# LM3404.net
KiCad netlist of a schematic drawn in EAGLE
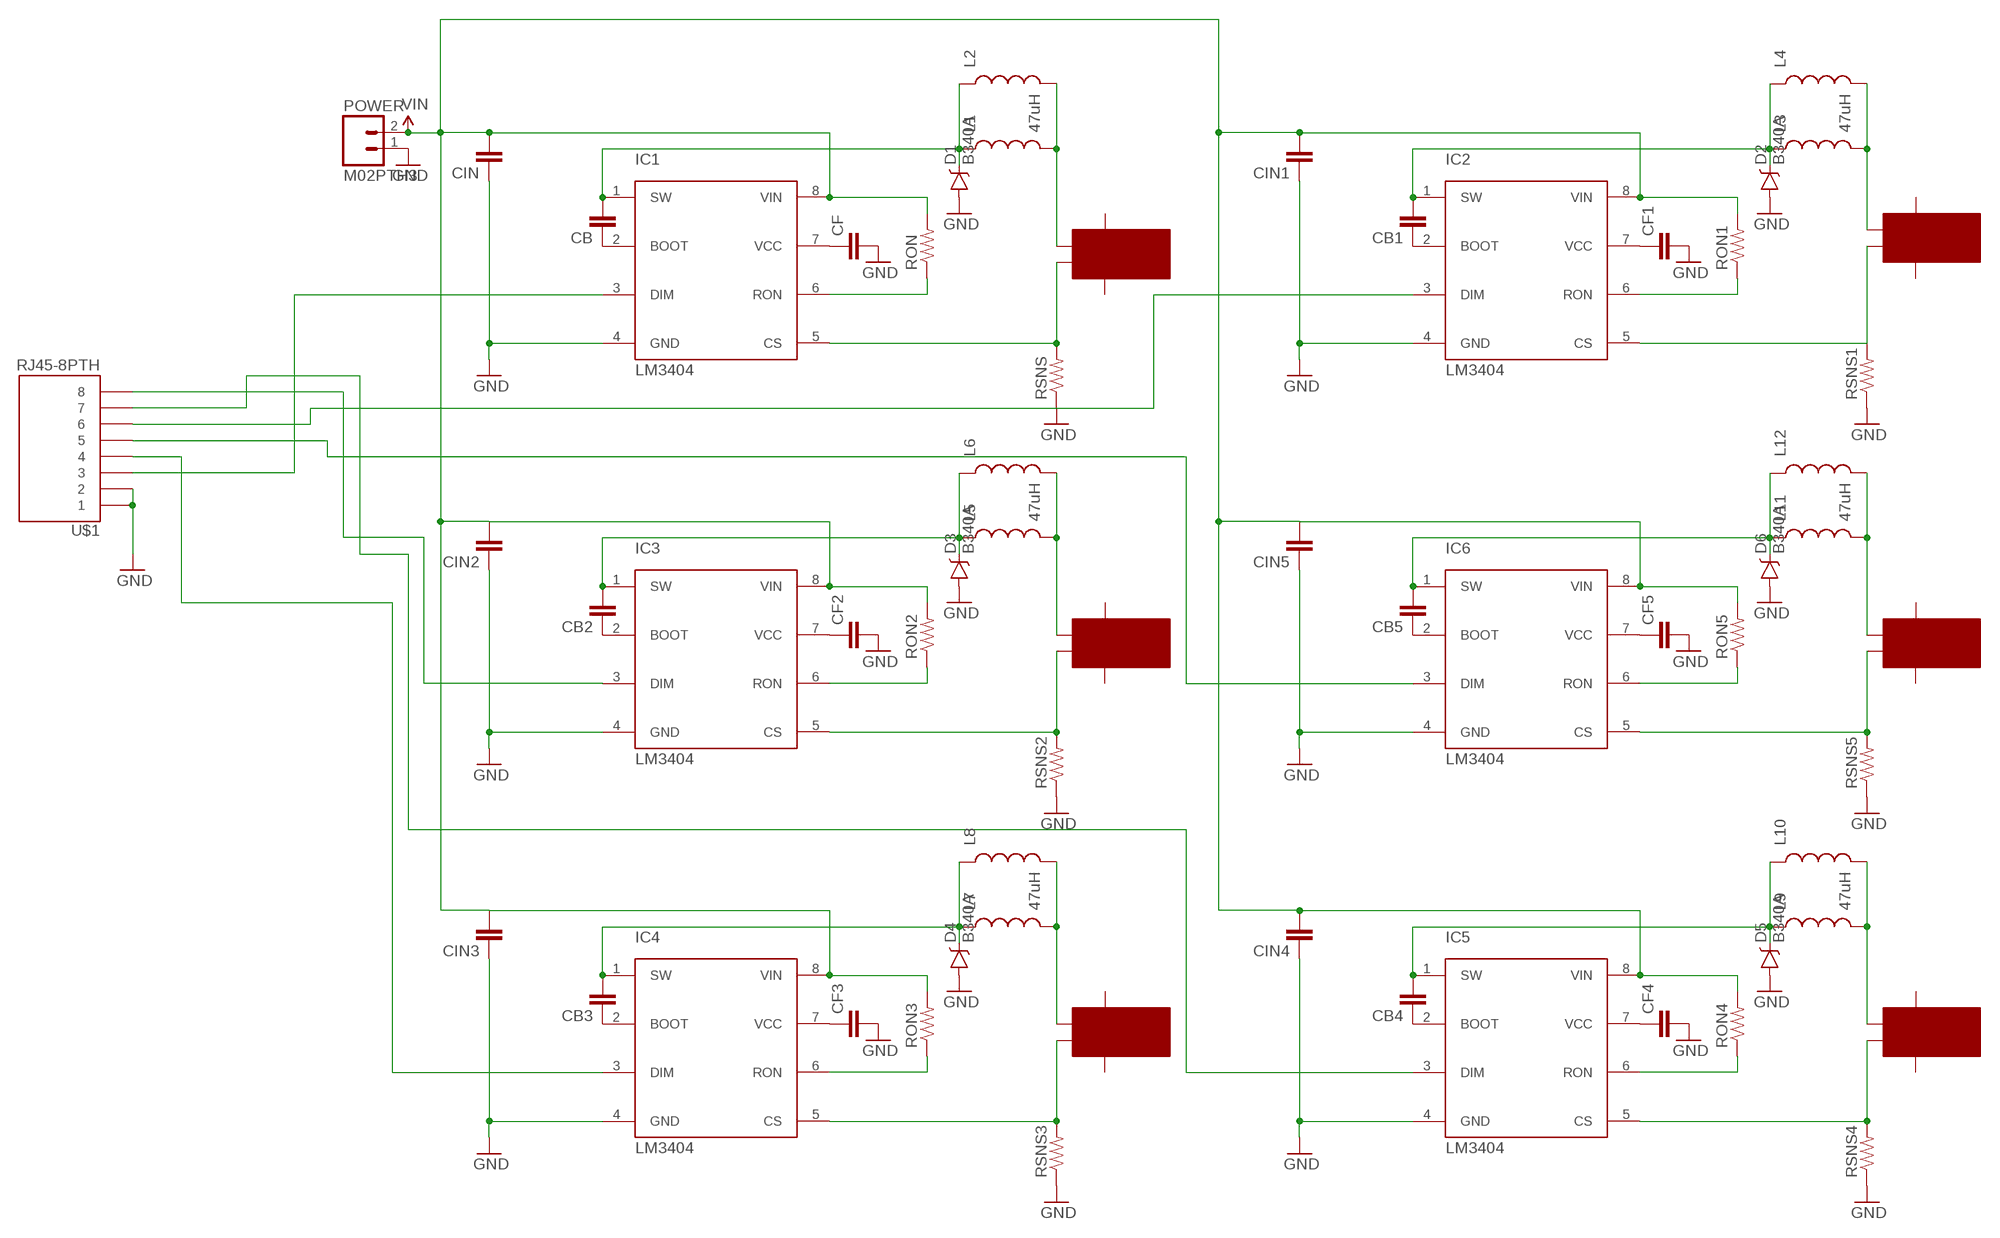
[diagram p0: schematic, sheet 1]

(export (version "E")
  (design (tool "Eeschema 10.0.6"))
  (components
    (comp (ref "CB")
      (value "CAP1206")
      (footprint "eagle-import:1206")
      (libsource (lib "eagle-import") (part "CAP1206"))
    )
    (comp (ref "CB1")
      (value "CAP1206")
      (footprint "eagle-import:1206")
      (libsource (lib "eagle-import") (part "CAP1206"))
    )
    (comp (ref "CB2")
      (value "CAP1206")
      (footprint "eagle-import:1206")
      (libsource (lib "eagle-import") (part "CAP1206"))
    )
    (comp (ref "CB3")
      (value "CAP1206")
      (footprint "eagle-import:1206")
      (libsource (lib "eagle-import") (part "CAP1206"))
    )
    (comp (ref "CB4")
      (value "CAP1206")
      (footprint "eagle-import:1206")
      (libsource (lib "eagle-import") (part "CAP1206"))
    )
    (comp (ref "CB5")
      (value "CAP1206")
      (footprint "eagle-import:1206")
      (libsource (lib "eagle-import") (part "CAP1206"))
    )
    (comp (ref "CF")
      (value "CAP1206")
      (footprint "eagle-import:1206")
      (libsource (lib "eagle-import") (part "CAP1206"))
    )
    (comp (ref "CF1")
      (value "CAP1206")
      (footprint "eagle-import:1206")
      (libsource (lib "eagle-import") (part "CAP1206"))
    )
    (comp (ref "CF2")
      (value "CAP1206")
      (footprint "eagle-import:1206")
      (libsource (lib "eagle-import") (part "CAP1206"))
    )
    (comp (ref "CF3")
      (value "CAP1206")
      (footprint "eagle-import:1206")
      (libsource (lib "eagle-import") (part "CAP1206"))
    )
    (comp (ref "CF4")
      (value "CAP1206")
      (footprint "eagle-import:1206")
      (libsource (lib "eagle-import") (part "CAP1206"))
    )
    (comp (ref "CF5")
      (value "CAP1206")
      (footprint "eagle-import:1206")
      (libsource (lib "eagle-import") (part "CAP1206"))
    )
    (comp (ref "CIN")
      (value "CAP1206")
      (footprint "eagle-import:1206")
      (libsource (lib "eagle-import") (part "CAP1206"))
    )
    (comp (ref "CIN1")
      (value "CAP1206")
      (footprint "eagle-import:1206")
      (libsource (lib "eagle-import") (part "CAP1206"))
    )
    (comp (ref "CIN2")
      (value "CAP1206")
      (footprint "eagle-import:1206")
      (libsource (lib "eagle-import") (part "CAP1206"))
    )
    (comp (ref "CIN3")
      (value "CAP1206")
      (footprint "eagle-import:1206")
      (libsource (lib "eagle-import") (part "CAP1206"))
    )
    (comp (ref "CIN4")
      (value "CAP1206")
      (footprint "eagle-import:1206")
      (libsource (lib "eagle-import") (part "CAP1206"))
    )
    (comp (ref "CIN5")
      (value "CAP1206")
      (footprint "eagle-import:1206")
      (libsource (lib "eagle-import") (part "CAP1206"))
    )
    (comp (ref "D1")
      (value "B340A")
      (footprint "eagle-import:SMA-DIODE")
      (libsource (lib "eagle-import") (part "DIODE-SCHOTTKY-B340A"))
    )
    (comp (ref "D2")
      (value "B340A")
      (footprint "eagle-import:SMA-DIODE")
      (libsource (lib "eagle-import") (part "DIODE-SCHOTTKY-B340A"))
    )
    (comp (ref "D3")
      (value "B340A")
      (footprint "eagle-import:SMA-DIODE")
      (libsource (lib "eagle-import") (part "DIODE-SCHOTTKY-B340A"))
    )
    (comp (ref "D4")
      (value "B340A")
      (footprint "eagle-import:SMA-DIODE")
      (libsource (lib "eagle-import") (part "DIODE-SCHOTTKY-B340A"))
    )
    (comp (ref "D5")
      (value "B340A")
      (footprint "eagle-import:SMA-DIODE")
      (libsource (lib "eagle-import") (part "DIODE-SCHOTTKY-B340A"))
    )
    (comp (ref "D6")
      (value "B340A")
      (footprint "eagle-import:SMA-DIODE")
      (libsource (lib "eagle-import") (part "DIODE-SCHOTTKY-B340A"))
    )
    (comp (ref "IC1")
      (value "LM3404")
      (footprint "eagle-import:SO8")
      (libsource (lib "eagle-import") (part "LM3404"))
    )
    (comp (ref "IC2")
      (value "LM3404")
      (footprint "eagle-import:SO8")
      (libsource (lib "eagle-import") (part "LM3404"))
    )
    (comp (ref "IC3")
      (value "LM3404")
      (footprint "eagle-import:SO8")
      (libsource (lib "eagle-import") (part "LM3404"))
    )
    (comp (ref "IC4")
      (value "LM3404")
      (footprint "eagle-import:SO8")
      (libsource (lib "eagle-import") (part "LM3404"))
    )
    (comp (ref "IC5")
      (value "LM3404")
      (footprint "eagle-import:SO8")
      (libsource (lib "eagle-import") (part "LM3404"))
    )
    (comp (ref "IC6")
      (value "LM3404")
      (footprint "eagle-import:SO8")
      (libsource (lib "eagle-import") (part "LM3404"))
    )
    (comp (ref "L1")
      (value "47uH")
      (footprint "eagle-import:CR75")
      (libsource (lib "eagle-import") (part "SparkFun-Passives_INDUCTOR68UH-1A"))
    )
    (comp (ref "L2")
      (value "INDUCTORSDR1105")
      (footprint "eagle-import:B82462G")
      (libsource (lib "eagle-import") (part "INDUCTORSDR1105"))
    )
    (comp (ref "L3")
      (value "47uH")
      (footprint "eagle-import:CR75")
      (libsource (lib "eagle-import") (part "SparkFun-Passives_INDUCTOR68UH-1A"))
    )
    (comp (ref "L4")
      (value "INDUCTORSDR1105")
      (footprint "eagle-import:B82462G")
      (libsource (lib "eagle-import") (part "INDUCTORSDR1105"))
    )
    (comp (ref "L5")
      (value "47uH")
      (footprint "eagle-import:CR75")
      (libsource (lib "eagle-import") (part "SparkFun-Passives_INDUCTOR68UH-1A"))
    )
    (comp (ref "L6")
      (value "INDUCTORSDR1105")
      (footprint "eagle-import:B82462G")
      (libsource (lib "eagle-import") (part "INDUCTORSDR1105"))
    )
    (comp (ref "L7")
      (value "47uH")
      (footprint "eagle-import:CR75")
      (libsource (lib "eagle-import") (part "SparkFun-Passives_INDUCTOR68UH-1A"))
    )
    (comp (ref "L8")
      (value "INDUCTORSDR1105")
      (footprint "eagle-import:B82462G")
      (libsource (lib "eagle-import") (part "INDUCTORSDR1105"))
    )
    (comp (ref "L9")
      (value "47uH")
      (footprint "eagle-import:CR75")
      (libsource (lib "eagle-import") (part "SparkFun-Passives_INDUCTOR68UH-1A"))
    )
    (comp (ref "L10")
      (value "INDUCTORSDR1105")
      (footprint "eagle-import:B82462G")
      (libsource (lib "eagle-import") (part "INDUCTORSDR1105"))
    )
    (comp (ref "L11")
      (value "47uH")
      (footprint "eagle-import:CR75")
      (libsource (lib "eagle-import") (part "SparkFun-Passives_INDUCTOR68UH-1A"))
    )
    (comp (ref "L12")
      (value "INDUCTORSDR1105")
      (footprint "eagle-import:B82462G")
      (libsource (lib "eagle-import") (part "INDUCTORSDR1105"))
    )
    (comp (ref "POWER")
      (value "M02PTH3")
      (footprint "eagle-import:1X02_LONGPADS")
      (libsource (lib "eagle-import") (part "M02PTH3"))
    )
    (comp (ref "RON")
      (value "RESISTOR1206")
      (footprint "eagle-import:1206")
      (libsource (lib "eagle-import") (part "RESISTOR1206"))
    )
    (comp (ref "RON1")
      (value "RESISTOR1206")
      (footprint "eagle-import:1206")
      (libsource (lib "eagle-import") (part "RESISTOR1206"))
    )
    (comp (ref "RON2")
      (value "RESISTOR1206")
      (footprint "eagle-import:1206")
      (libsource (lib "eagle-import") (part "RESISTOR1206"))
    )
    (comp (ref "RON3")
      (value "RESISTOR1206")
      (footprint "eagle-import:1206")
      (libsource (lib "eagle-import") (part "RESISTOR1206"))
    )
    (comp (ref "RON4")
      (value "RESISTOR1206")
      (footprint "eagle-import:1206")
      (libsource (lib "eagle-import") (part "RESISTOR1206"))
    )
    (comp (ref "RON5")
      (value "RESISTOR1206")
      (footprint "eagle-import:1206")
      (libsource (lib "eagle-import") (part "RESISTOR1206"))
    )
    (comp (ref "RSNS")
      (value "RESISTOR1206")
      (footprint "eagle-import:1206")
      (libsource (lib "eagle-import") (part "RESISTOR1206"))
    )
    (comp (ref "RSNS1")
      (value "RESISTOR1206")
      (footprint "eagle-import:1206")
      (libsource (lib "eagle-import") (part "RESISTOR1206"))
    )
    (comp (ref "RSNS2")
      (value "RESISTOR1206")
      (footprint "eagle-import:1206")
      (libsource (lib "eagle-import") (part "RESISTOR1206"))
    )
    (comp (ref "RSNS3")
      (value "RESISTOR1206")
      (footprint "eagle-import:1206")
      (libsource (lib "eagle-import") (part "RESISTOR1206"))
    )
    (comp (ref "RSNS4")
      (value "RESISTOR1206")
      (footprint "eagle-import:1206")
      (libsource (lib "eagle-import") (part "RESISTOR1206"))
    )
    (comp (ref "RSNS5")
      (value "RESISTOR1206")
      (footprint "eagle-import:1206")
      (libsource (lib "eagle-import") (part "RESISTOR1206"))
    )
    (comp (ref "U$1")
      (value "RJ45-8PTH")
      (footprint "eagle-import:RJ45-8")
      (libsource (lib "eagle-import") (part "RJ45-8PTH"))
    )
    (comp (ref "U$2")
      (value "RCA_JACK")
      (footprint "eagle-import:RCA_JACK")
      (libsource (lib "eagle-import") (part "RCA_JACK"))
    )
    (comp (ref "U$3")
      (value "RCA_JACK")
      (footprint "eagle-import:RCA_JACK")
      (libsource (lib "eagle-import") (part "RCA_JACK"))
    )
    (comp (ref "U$4")
      (value "RCA_JACK")
      (footprint "eagle-import:RCA_JACK")
      (libsource (lib "eagle-import") (part "RCA_JACK"))
    )
    (comp (ref "U$5")
      (value "RCA_JACK")
      (footprint "eagle-import:RCA_JACK")
      (libsource (lib "eagle-import") (part "RCA_JACK"))
    )
    (comp (ref "U$6")
      (value "RCA_JACK")
      (footprint "eagle-import:RCA_JACK")
      (libsource (lib "eagle-import") (part "RCA_JACK"))
    )
    (comp (ref "U$7")
      (value "RCA_JACK")
      (footprint "eagle-import:RCA_JACK")
      (libsource (lib "eagle-import") (part "RCA_JACK"))
    )
  )
  (nets
    (net (code "1") (name "GND") (class "Default")
      (node (ref "CF") (pin "2") (pinfunction "2_2") (pintype "passive"))
      (node (ref "CF1") (pin "2") (pinfunction "2_2") (pintype "passive"))
      (node (ref "CF2") (pin "2") (pinfunction "2_2") (pintype "passive"))
      (node (ref "CF3") (pin "2") (pinfunction "2_2") (pintype "passive"))
      (node (ref "CF4") (pin "2") (pinfunction "2_2") (pintype "passive"))
      (node (ref "CF5") (pin "2") (pinfunction "2_2") (pintype "passive"))
      (node (ref "CIN") (pin "1") (pinfunction "1_1") (pintype "passive"))
      (node (ref "CIN1") (pin "1") (pinfunction "1_1") (pintype "passive"))
      (node (ref "CIN2") (pin "1") (pinfunction "1_1") (pintype "passive"))
      (node (ref "CIN3") (pin "1") (pinfunction "1_1") (pintype "passive"))
      (node (ref "CIN4") (pin "1") (pinfunction "1_1") (pintype "passive"))
      (node (ref "CIN5") (pin "1") (pinfunction "1_1") (pintype "passive"))
      (node (ref "D1") (pin "A") (pinfunction "A_A") (pintype "passive"))
      (node (ref "D2") (pin "A") (pinfunction "A_A") (pintype "passive"))
      (node (ref "D3") (pin "A") (pinfunction "A_A") (pintype "passive"))
      (node (ref "D4") (pin "A") (pinfunction "A_A") (pintype "passive"))
      (node (ref "D5") (pin "A") (pinfunction "A_A") (pintype "passive"))
      (node (ref "D6") (pin "A") (pinfunction "A_A") (pintype "passive"))
      (node (ref "IC1") (pin "4") (pinfunction "GND_4") (pintype "bidirectional"))
      (node (ref "IC2") (pin "4") (pinfunction "GND_4") (pintype "bidirectional"))
      (node (ref "IC3") (pin "4") (pinfunction "GND_4") (pintype "bidirectional"))
      (node (ref "IC4") (pin "4") (pinfunction "GND_4") (pintype "bidirectional"))
      (node (ref "IC5") (pin "4") (pinfunction "GND_4") (pintype "bidirectional"))
      (node (ref "IC6") (pin "4") (pinfunction "GND_4") (pintype "bidirectional"))
      (node (ref "POWER") (pin "1") (pinfunction "1_1") (pintype "passive"))
      (node (ref "RSNS") (pin "1") (pinfunction "1_1") (pintype "passive"))
      (node (ref "RSNS1") (pin "1") (pinfunction "1_1") (pintype "passive"))
      (node (ref "RSNS2") (pin "1") (pinfunction "1_1") (pintype "passive"))
      (node (ref "RSNS3") (pin "1") (pinfunction "1_1") (pintype "passive"))
      (node (ref "RSNS4") (pin "1") (pinfunction "1_1") (pintype "passive"))
      (node (ref "RSNS5") (pin "1") (pinfunction "1_1") (pintype "passive"))
      (node (ref "U$1") (pin "1") (pinfunction "1_1") (pintype "bidirectional"))
      (node (ref "U$1") (pin "2") (pinfunction "2_2") (pintype "bidirectional"))
    )
    (net (code "2") (name "Net-(IC1-BOOT)") (class "Default")
      (node (ref "CB") (pin "1") (pinfunction "1_1") (pintype "passive"))
      (node (ref "IC1") (pin "2") (pinfunction "BOOT_2") (pintype "bidirectional"))
    )
    (net (code "3") (name "Net-(IC1-CS)") (class "Default")
      (node (ref "IC1") (pin "5") (pinfunction "CS_5") (pintype "bidirectional"))
      (node (ref "RSNS") (pin "2") (pinfunction "2_2") (pintype "passive"))
      (node (ref "U$7") (pin "INNER") (pinfunction "INNER_INNER") (pintype "bidirectional"))
    )
    (net (code "4") (name "Net-(IC1-DIM)") (class "Default")
      (node (ref "IC1") (pin "3") (pinfunction "DIM_3") (pintype "bidirectional"))
      (node (ref "U$1") (pin "3") (pinfunction "3_3") (pintype "bidirectional"))
    )
    (net (code "5") (name "Net-(IC1-RON)") (class "Default")
      (node (ref "IC1") (pin "6") (pinfunction "RON_6") (pintype "bidirectional"))
      (node (ref "RON") (pin "1") (pinfunction "1_1") (pintype "passive"))
    )
    (net (code "6") (name "Net-(IC1-SW)") (class "Default")
      (node (ref "CB") (pin "2") (pinfunction "2_2") (pintype "passive"))
      (node (ref "D1") (pin "C") (pinfunction "C_C") (pintype "passive"))
      (node (ref "IC1") (pin "1") (pinfunction "SW_1") (pintype "bidirectional"))
      (node (ref "L1") (pin "P$1") (pinfunction "1_P$1") (pintype "passive"))
      (node (ref "L2") (pin "P$1") (pinfunction "1_P$1") (pintype "passive"))
    )
    (net (code "7") (name "Net-(IC1-VCC)") (class "Default")
      (node (ref "CF") (pin "1") (pinfunction "1_1") (pintype "passive"))
      (node (ref "IC1") (pin "7") (pinfunction "VCC_7") (pintype "bidirectional"))
    )
    (net (code "8") (name "Net-(IC2-BOOT)") (class "Default")
      (node (ref "CB1") (pin "1") (pinfunction "1_1") (pintype "passive"))
      (node (ref "IC2") (pin "2") (pinfunction "BOOT_2") (pintype "bidirectional"))
    )
    (net (code "9") (name "Net-(IC2-CS)") (class "Default")
      (node (ref "IC2") (pin "5") (pinfunction "CS_5") (pintype "bidirectional"))
      (node (ref "RSNS1") (pin "2") (pinfunction "2_2") (pintype "passive"))
      (node (ref "U$2") (pin "INNER") (pinfunction "INNER_INNER") (pintype "bidirectional"))
    )
    (net (code "10") (name "Net-(IC2-DIM)") (class "Default")
      (node (ref "IC2") (pin "3") (pinfunction "DIM_3") (pintype "bidirectional"))
      (node (ref "U$1") (pin "6") (pinfunction "6_6") (pintype "bidirectional"))
    )
    (net (code "11") (name "Net-(IC2-RON)") (class "Default")
      (node (ref "IC2") (pin "6") (pinfunction "RON_6") (pintype "bidirectional"))
      (node (ref "RON1") (pin "1") (pinfunction "1_1") (pintype "passive"))
    )
    (net (code "12") (name "Net-(IC2-SW)") (class "Default")
      (node (ref "CB1") (pin "2") (pinfunction "2_2") (pintype "passive"))
      (node (ref "D2") (pin "C") (pinfunction "C_C") (pintype "passive"))
      (node (ref "IC2") (pin "1") (pinfunction "SW_1") (pintype "bidirectional"))
      (node (ref "L3") (pin "P$1") (pinfunction "1_P$1") (pintype "passive"))
      (node (ref "L4") (pin "P$1") (pinfunction "1_P$1") (pintype "passive"))
    )
    (net (code "13") (name "Net-(IC2-VCC)") (class "Default")
      (node (ref "CF1") (pin "1") (pinfunction "1_1") (pintype "passive"))
      (node (ref "IC2") (pin "7") (pinfunction "VCC_7") (pintype "bidirectional"))
    )
    (net (code "14") (name "Net-(IC3-BOOT)") (class "Default")
      (node (ref "CB2") (pin "1") (pinfunction "1_1") (pintype "passive"))
      (node (ref "IC3") (pin "2") (pinfunction "BOOT_2") (pintype "bidirectional"))
    )
    (net (code "15") (name "Net-(IC3-CS)") (class "Default")
      (node (ref "IC3") (pin "5") (pinfunction "CS_5") (pintype "bidirectional"))
      (node (ref "RSNS2") (pin "2") (pinfunction "2_2") (pintype "passive"))
      (node (ref "U$6") (pin "INNER") (pinfunction "INNER_INNER") (pintype "bidirectional"))
    )
    (net (code "16") (name "Net-(IC3-DIM)") (class "Default")
      (node (ref "IC3") (pin "3") (pinfunction "DIM_3") (pintype "bidirectional"))
      (node (ref "U$1") (pin "8") (pinfunction "8_8") (pintype "bidirectional"))
    )
    (net (code "17") (name "Net-(IC3-RON)") (class "Default")
      (node (ref "IC3") (pin "6") (pinfunction "RON_6") (pintype "bidirectional"))
      (node (ref "RON2") (pin "1") (pinfunction "1_1") (pintype "passive"))
    )
    (net (code "18") (name "Net-(IC3-SW)") (class "Default")
      (node (ref "CB2") (pin "2") (pinfunction "2_2") (pintype "passive"))
      (node (ref "D3") (pin "C") (pinfunction "C_C") (pintype "passive"))
      (node (ref "IC3") (pin "1") (pinfunction "SW_1") (pintype "bidirectional"))
      (node (ref "L5") (pin "P$1") (pinfunction "1_P$1") (pintype "passive"))
      (node (ref "L6") (pin "P$1") (pinfunction "1_P$1") (pintype "passive"))
    )
    (net (code "19") (name "Net-(IC3-VCC)") (class "Default")
      (node (ref "CF2") (pin "1") (pinfunction "1_1") (pintype "passive"))
      (node (ref "IC3") (pin "7") (pinfunction "VCC_7") (pintype "bidirectional"))
    )
    (net (code "20") (name "Net-(IC4-BOOT)") (class "Default")
      (node (ref "CB3") (pin "1") (pinfunction "1_1") (pintype "passive"))
      (node (ref "IC4") (pin "2") (pinfunction "BOOT_2") (pintype "bidirectional"))
    )
    (net (code "21") (name "Net-(IC4-CS)") (class "Default")
      (node (ref "IC4") (pin "5") (pinfunction "CS_5") (pintype "bidirectional"))
      (node (ref "RSNS3") (pin "2") (pinfunction "2_2") (pintype "passive"))
      (node (ref "U$5") (pin "INNER") (pinfunction "INNER_INNER") (pintype "bidirectional"))
    )
    (net (code "22") (name "Net-(IC4-DIM)") (class "Default")
      (node (ref "IC4") (pin "3") (pinfunction "DIM_3") (pintype "bidirectional"))
      (node (ref "U$1") (pin "4") (pinfunction "4_4") (pintype "bidirectional"))
    )
    (net (code "23") (name "Net-(IC4-RON)") (class "Default")
      (node (ref "IC4") (pin "6") (pinfunction "RON_6") (pintype "bidirectional"))
      (node (ref "RON3") (pin "1") (pinfunction "1_1") (pintype "passive"))
    )
    (net (code "24") (name "Net-(IC4-SW)") (class "Default")
      (node (ref "CB3") (pin "2") (pinfunction "2_2") (pintype "passive"))
      (node (ref "D4") (pin "C") (pinfunction "C_C") (pintype "passive"))
      (node (ref "IC4") (pin "1") (pinfunction "SW_1") (pintype "bidirectional"))
      (node (ref "L7") (pin "P$1") (pinfunction "1_P$1") (pintype "passive"))
      (node (ref "L8") (pin "P$1") (pinfunction "1_P$1") (pintype "passive"))
    )
    (net (code "25") (name "Net-(IC4-VCC)") (class "Default")
      (node (ref "CF3") (pin "1") (pinfunction "1_1") (pintype "passive"))
      (node (ref "IC4") (pin "7") (pinfunction "VCC_7") (pintype "bidirectional"))
    )
    (net (code "26") (name "Net-(IC5-BOOT)") (class "Default")
      (node (ref "CB4") (pin "1") (pinfunction "1_1") (pintype "passive"))
      (node (ref "IC5") (pin "2") (pinfunction "BOOT_2") (pintype "bidirectional"))
    )
    (net (code "27") (name "Net-(IC5-CS)") (class "Default")
      (node (ref "IC5") (pin "5") (pinfunction "CS_5") (pintype "bidirectional"))
      (node (ref "RSNS4") (pin "2") (pinfunction "2_2") (pintype "passive"))
      (node (ref "U$4") (pin "INNER") (pinfunction "INNER_INNER") (pintype "bidirectional"))
    )
    (net (code "28") (name "Net-(IC5-DIM)") (class "Default")
      (node (ref "IC5") (pin "3") (pinfunction "DIM_3") (pintype "bidirectional"))
      (node (ref "U$1") (pin "7") (pinfunction "7_7") (pintype "bidirectional"))
    )
    (net (code "29") (name "Net-(IC5-RON)") (class "Default")
      (node (ref "IC5") (pin "6") (pinfunction "RON_6") (pintype "bidirectional"))
      (node (ref "RON4") (pin "1") (pinfunction "1_1") (pintype "passive"))
    )
    (net (code "30") (name "Net-(IC5-SW)") (class "Default")
      (node (ref "CB4") (pin "2") (pinfunction "2_2") (pintype "passive"))
      (node (ref "D5") (pin "C") (pinfunction "C_C") (pintype "passive"))
      (node (ref "IC5") (pin "1") (pinfunction "SW_1") (pintype "bidirectional"))
      (node (ref "L10") (pin "P$1") (pinfunction "1_P$1") (pintype "passive"))
      (node (ref "L9") (pin "P$1") (pinfunction "1_P$1") (pintype "passive"))
    )
    (net (code "31") (name "Net-(IC5-VCC)") (class "Default")
      (node (ref "CF4") (pin "1") (pinfunction "1_1") (pintype "passive"))
      (node (ref "IC5") (pin "7") (pinfunction "VCC_7") (pintype "bidirectional"))
    )
    (net (code "32") (name "Net-(IC6-BOOT)") (class "Default")
      (node (ref "CB5") (pin "1") (pinfunction "1_1") (pintype "passive"))
      (node (ref "IC6") (pin "2") (pinfunction "BOOT_2") (pintype "bidirectional"))
    )
    (net (code "33") (name "Net-(IC6-CS)") (class "Default")
      (node (ref "IC6") (pin "5") (pinfunction "CS_5") (pintype "bidirectional"))
      (node (ref "RSNS5") (pin "2") (pinfunction "2_2") (pintype "passive"))
      (node (ref "U$3") (pin "INNER") (pinfunction "INNER_INNER") (pintype "bidirectional"))
    )
    (net (code "34") (name "Net-(IC6-DIM)") (class "Default")
      (node (ref "IC6") (pin "3") (pinfunction "DIM_3") (pintype "bidirectional"))
      (node (ref "U$1") (pin "5") (pinfunction "5_5") (pintype "bidirectional"))
    )
    (net (code "35") (name "Net-(IC6-RON)") (class "Default")
      (node (ref "IC6") (pin "6") (pinfunction "RON_6") (pintype "bidirectional"))
      (node (ref "RON5") (pin "1") (pinfunction "1_1") (pintype "passive"))
    )
    (net (code "36") (name "Net-(IC6-SW)") (class "Default")
      (node (ref "CB5") (pin "2") (pinfunction "2_2") (pintype "passive"))
      (node (ref "D6") (pin "C") (pinfunction "C_C") (pintype "passive"))
      (node (ref "IC6") (pin "1") (pinfunction "SW_1") (pintype "bidirectional"))
      (node (ref "L11") (pin "P$1") (pinfunction "1_P$1") (pintype "passive"))
      (node (ref "L12") (pin "P$1") (pinfunction "1_P$1") (pintype "passive"))
    )
    (net (code "37") (name "Net-(IC6-VCC)") (class "Default")
      (node (ref "CF5") (pin "1") (pinfunction "1_1") (pintype "passive"))
      (node (ref "IC6") (pin "7") (pinfunction "VCC_7") (pintype "bidirectional"))
    )
    (net (code "38") (name "Net-(L1-2)") (class "Default")
      (node (ref "L1") (pin "P$2") (pinfunction "2_P$2") (pintype "passive"))
      (node (ref "L2") (pin "P$2") (pinfunction "2_P$2") (pintype "passive"))
      (node (ref "U$7") (pin "SIG") (pinfunction "SIG_SIG") (pintype "bidirectional"))
    )
    (net (code "39") (name "Net-(L3-2)") (class "Default")
      (node (ref "L3") (pin "P$2") (pinfunction "2_P$2") (pintype "passive"))
      (node (ref "L4") (pin "P$2") (pinfunction "2_P$2") (pintype "passive"))
      (node (ref "U$2") (pin "SIG") (pinfunction "SIG_SIG") (pintype "bidirectional"))
    )
    (net (code "40") (name "Net-(L5-2)") (class "Default")
      (node (ref "L5") (pin "P$2") (pinfunction "2_P$2") (pintype "passive"))
      (node (ref "L6") (pin "P$2") (pinfunction "2_P$2") (pintype "passive"))
      (node (ref "U$6") (pin "SIG") (pinfunction "SIG_SIG") (pintype "bidirectional"))
    )
    (net (code "41") (name "Net-(L7-2)") (class "Default")
      (node (ref "L7") (pin "P$2") (pinfunction "2_P$2") (pintype "passive"))
      (node (ref "L8") (pin "P$2") (pinfunction "2_P$2") (pintype "passive"))
      (node (ref "U$5") (pin "SIG") (pinfunction "SIG_SIG") (pintype "bidirectional"))
    )
    (net (code "42") (name "Net-(L10-2)") (class "Default")
      (node (ref "L10") (pin "P$2") (pinfunction "2_P$2") (pintype "passive"))
      (node (ref "L9") (pin "P$2") (pinfunction "2_P$2") (pintype "passive"))
      (node (ref "U$4") (pin "SIG") (pinfunction "SIG_SIG") (pintype "bidirectional"))
    )
    (net (code "43") (name "Net-(L11-2)") (class "Default")
      (node (ref "L11") (pin "P$2") (pinfunction "2_P$2") (pintype "passive"))
      (node (ref "L12") (pin "P$2") (pinfunction "2_P$2") (pintype "passive"))
      (node (ref "U$3") (pin "SIG") (pinfunction "SIG_SIG") (pintype "bidirectional"))
    )
    (net (code "44") (name "VIN") (class "Default")
      (node (ref "CIN") (pin "2") (pinfunction "2_2") (pintype "passive"))
      (node (ref "CIN1") (pin "2") (pinfunction "2_2") (pintype "passive"))
      (node (ref "CIN2") (pin "2") (pinfunction "2_2") (pintype "passive"))
      (node (ref "CIN3") (pin "2") (pinfunction "2_2") (pintype "passive"))
      (node (ref "CIN4") (pin "2") (pinfunction "2_2") (pintype "passive"))
      (node (ref "CIN5") (pin "2") (pinfunction "2_2") (pintype "passive"))
      (node (ref "IC1") (pin "8") (pinfunction "VIN_8") (pintype "bidirectional"))
      (node (ref "IC2") (pin "8") (pinfunction "VIN_8") (pintype "bidirectional"))
      (node (ref "IC3") (pin "8") (pinfunction "VIN_8") (pintype "bidirectional"))
      (node (ref "IC4") (pin "8") (pinfunction "VIN_8") (pintype "bidirectional"))
      (node (ref "IC5") (pin "8") (pinfunction "VIN_8") (pintype "bidirectional"))
      (node (ref "IC6") (pin "8") (pinfunction "VIN_8") (pintype "bidirectional"))
      (node (ref "POWER") (pin "2") (pinfunction "2_2") (pintype "passive"))
      (node (ref "RON") (pin "2") (pinfunction "2_2") (pintype "passive"))
      (node (ref "RON1") (pin "2") (pinfunction "2_2") (pintype "passive"))
      (node (ref "RON2") (pin "2") (pinfunction "2_2") (pintype "passive"))
      (node (ref "RON3") (pin "2") (pinfunction "2_2") (pintype "passive"))
      (node (ref "RON4") (pin "2") (pinfunction "2_2") (pintype "passive"))
      (node (ref "RON5") (pin "2") (pinfunction "2_2") (pintype "passive"))
    )
    (net (code "45") (name "unconnected-(U$2-PadSWA)") (class "Default")
      (node (ref "U$2") (pin "SWA") (pinfunction "SWA_SWA") (pintype "bidirectional"))
    )
    (net (code "46") (name "unconnected-(U$2-PadSWB)") (class "Default")
      (node (ref "U$2") (pin "SWB") (pinfunction "SWB_SWB") (pintype "bidirectional"))
    )
    (net (code "47") (name "unconnected-(U$3-PadSWA)") (class "Default")
      (node (ref "U$3") (pin "SWA") (pinfunction "SWA_SWA") (pintype "bidirectional"))
    )
    (net (code "48") (name "unconnected-(U$3-PadSWB)") (class "Default")
      (node (ref "U$3") (pin "SWB") (pinfunction "SWB_SWB") (pintype "bidirectional"))
    )
    (net (code "49") (name "unconnected-(U$4-PadSWA)") (class "Default")
      (node (ref "U$4") (pin "SWA") (pinfunction "SWA_SWA") (pintype "bidirectional"))
    )
    (net (code "50") (name "unconnected-(U$4-PadSWB)") (class "Default")
      (node (ref "U$4") (pin "SWB") (pinfunction "SWB_SWB") (pintype "bidirectional"))
    )
    (net (code "51") (name "unconnected-(U$5-PadSWA)") (class "Default")
      (node (ref "U$5") (pin "SWA") (pinfunction "SWA_SWA") (pintype "bidirectional"))
    )
    (net (code "52") (name "unconnected-(U$5-PadSWB)") (class "Default")
      (node (ref "U$5") (pin "SWB") (pinfunction "SWB_SWB") (pintype "bidirectional"))
    )
    (net (code "53") (name "unconnected-(U$6-PadSWA)") (class "Default")
      (node (ref "U$6") (pin "SWA") (pinfunction "SWA_SWA") (pintype "bidirectional"))
    )
    (net (code "54") (name "unconnected-(U$6-PadSWB)") (class "Default")
      (node (ref "U$6") (pin "SWB") (pinfunction "SWB_SWB") (pintype "bidirectional"))
    )
    (net (code "55") (name "unconnected-(U$7-PadSWA)") (class "Default")
      (node (ref "U$7") (pin "SWA") (pinfunction "SWA_SWA") (pintype "bidirectional"))
    )
    (net (code "56") (name "unconnected-(U$7-PadSWB)") (class "Default")
      (node (ref "U$7") (pin "SWB") (pinfunction "SWB_SWB") (pintype "bidirectional"))
    )
  )
)
